# IMU_CAN_Speed_Converter_Board_rev2.net
KiCad netlist of a schematic drawn in EAGLE
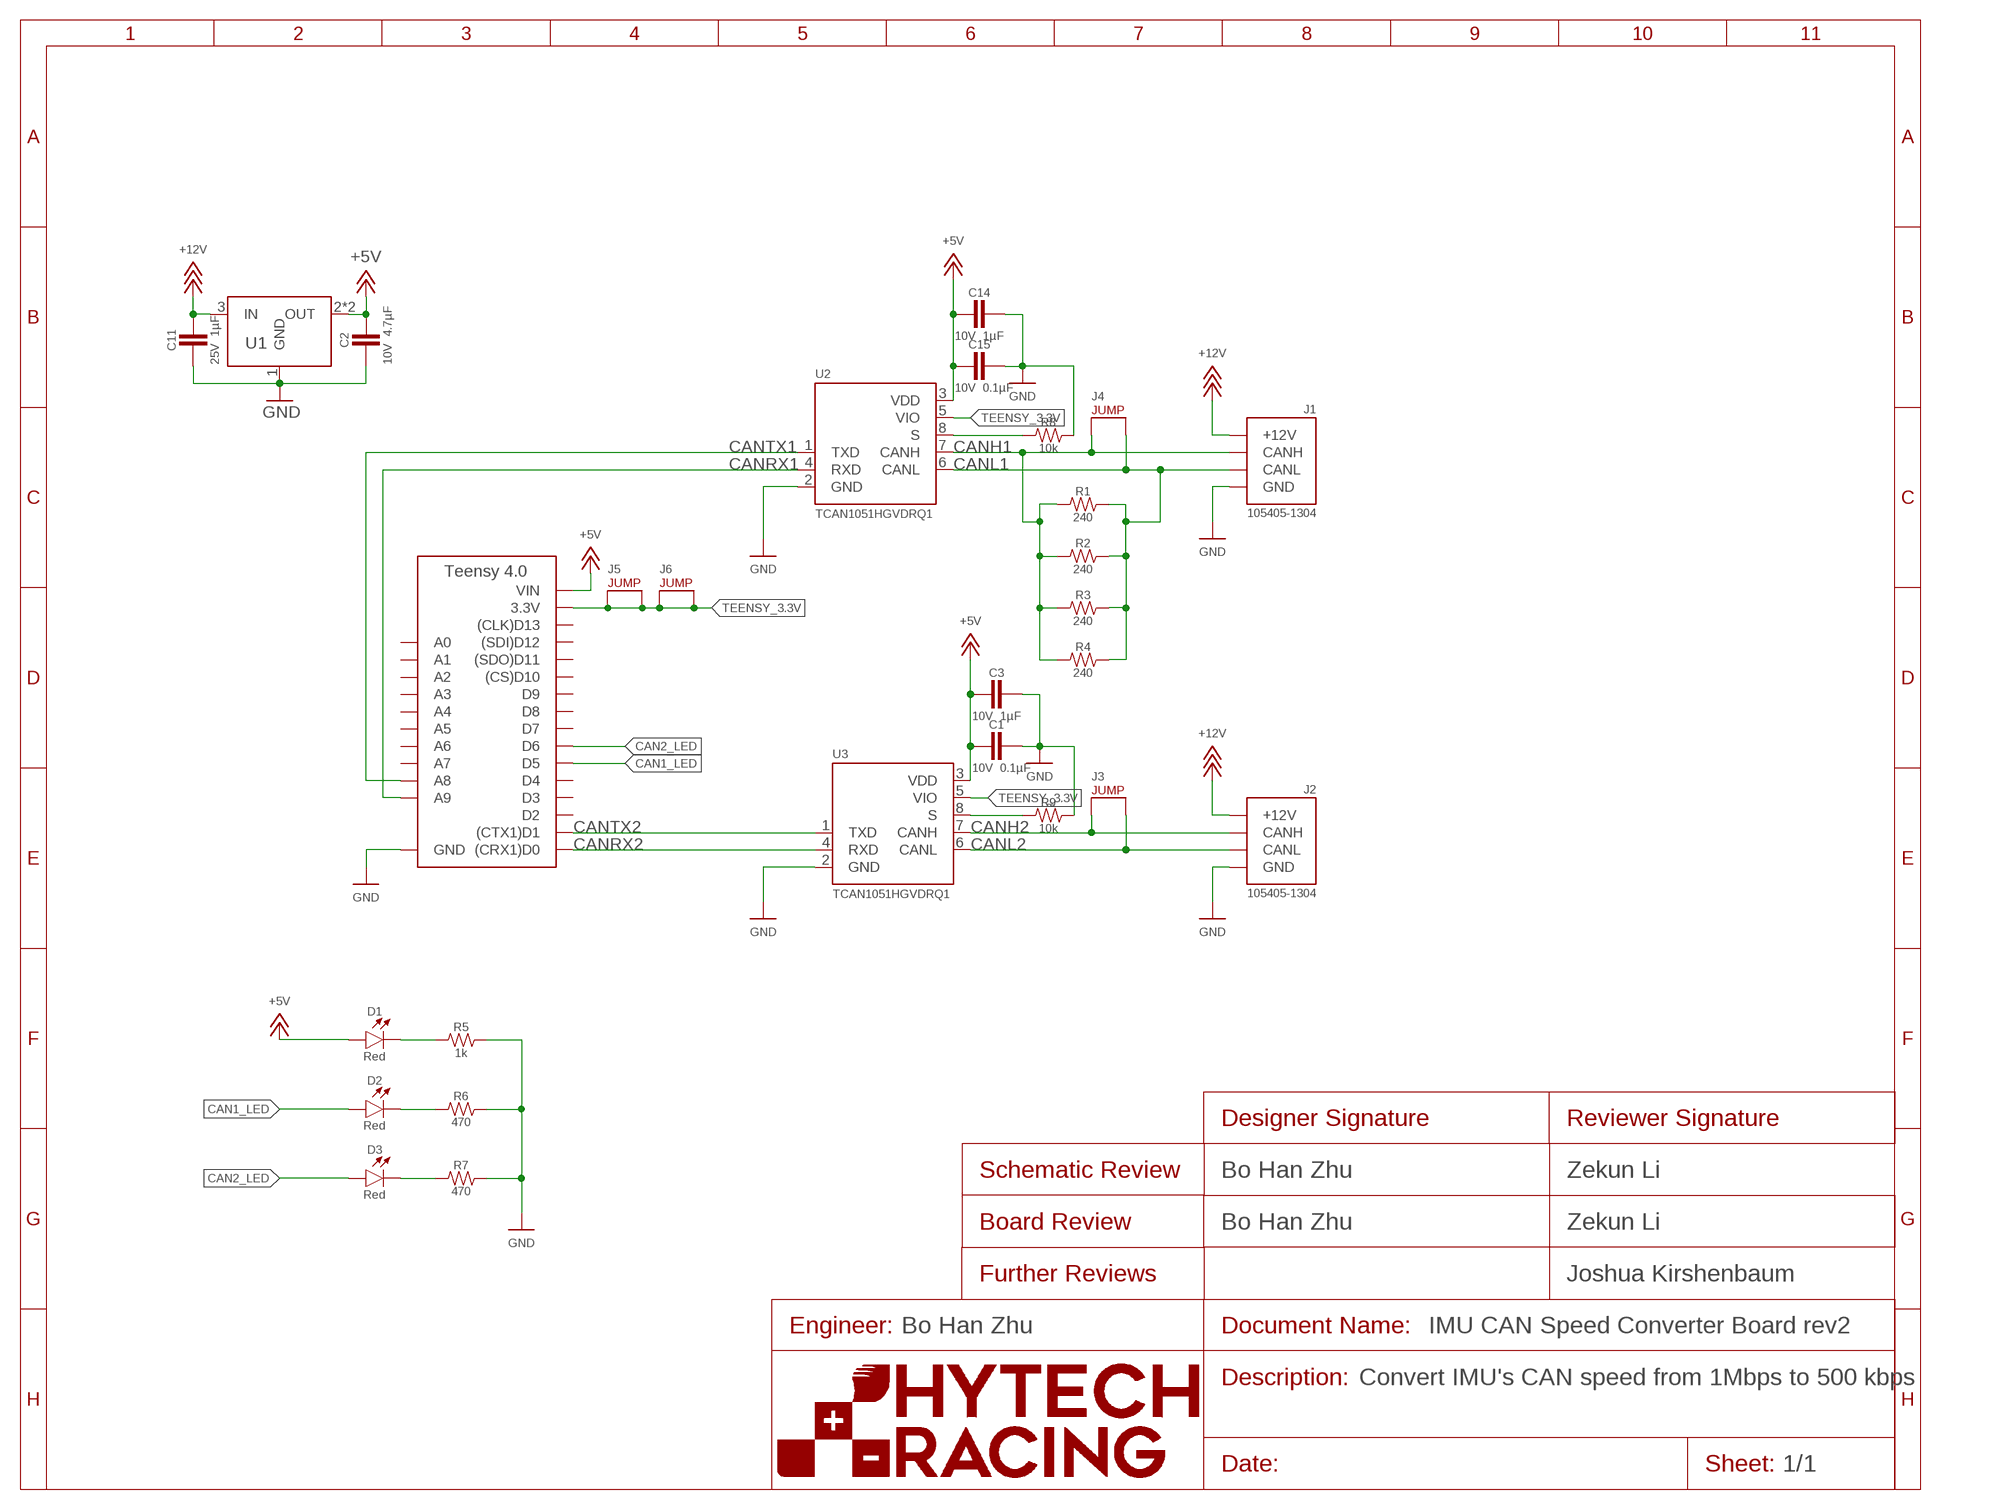
[diagram p0: schematic, sheet 1]

(export (version "E")
  (design (tool "Eeschema 10.0.6"))
  (components
    (comp (ref "A1")
      (value "TEENSY_4.0")
      (footprint "eagle-import:TEENSY_SHORT")
      (libsource (lib "eagle-import") (part "TEENSY_4.0"))
    )
    (comp (ref "C1")
      (value "CAPACITOR_0603_10V_0.1UF")
      (footprint "eagle-import:0603-CAP")
      (fields
        (field (name "CAPACITANCE") "0.1µF")
        (field (name "MANUFACTURER") "Vishay Vitramon")
        (field (name "MPN") "VJ0603Y104JXQPW1BC")
        (field (name "TOLERANCE") "5%")
        (field (name "VOLTAGE") "10V")
      )
      (libsource (lib "eagle-import") (part "CAPACITOR_?_060310V_0.1UF"))
    )
    (comp (ref "C2")
      (value "CAPACITOR_0603_10V_4.7UF")
      (footprint "eagle-import:0603-CAP")
      (fields
        (field (name "CAPACITANCE") "4.7µF")
        (field (name "MANUFACTURER") "Samsung Electro-Mechanics")
        (field (name "MPN") "CL10A475KP8NNNC")
        (field (name "TOLERANCE") "10%")
        (field (name "VOLTAGE") "10V")
      )
      (libsource (lib "eagle-import") (part "CAPACITOR_?_060310V_4.7UF"))
    )
    (comp (ref "C3")
      (value "CAPACITOR_0603_10V_1UF")
      (footprint "eagle-import:0603-CAP")
      (fields
        (field (name "CAPACITANCE") "1µF")
        (field (name "MANUFACTURER") "Yageo")
        (field (name "MPN") "CC0603KRX7R6BB105")
        (field (name "TOLERANCE") "10%")
        (field (name "VOLTAGE") "10V")
      )
      (libsource (lib "eagle-import") (part "CAPACITOR_?_060310V_1UF"))
    )
    (comp (ref "C11")
      (value "CAPACITOR_0603_25V_1UF")
      (footprint "eagle-import:0603-CAP")
      (fields
        (field (name "CAPACITANCE") "1µF")
        (field (name "MANUFACTURER") "Samsung Electro-Mechanics")
        (field (name "MPN") "CL10B105KA8NNNC")
        (field (name "TOLERANCE") "10%")
        (field (name "VOLTAGE") "25V")
      )
      (libsource (lib "eagle-import") (part "CAPACITOR_?_060325V_1UF"))
    )
    (comp (ref "C14")
      (value "CAPACITOR_0603_10V_1UF")
      (footprint "eagle-import:0603-CAP")
      (fields
        (field (name "CAPACITANCE") "1µF")
        (field (name "MANUFACTURER") "Yageo")
        (field (name "MPN") "CC0603KRX7R6BB105")
        (field (name "TOLERANCE") "10%")
        (field (name "VOLTAGE") "10V")
      )
      (libsource (lib "eagle-import") (part "CAPACITOR_?_060310V_1UF"))
    )
    (comp (ref "C15")
      (value "CAPACITOR_0603_10V_0.1UF")
      (footprint "eagle-import:0603-CAP")
      (fields
        (field (name "CAPACITANCE") "0.1µF")
        (field (name "MANUFACTURER") "Vishay Vitramon")
        (field (name "MPN") "VJ0603Y104JXQPW1BC")
        (field (name "TOLERANCE") "5%")
        (field (name "VOLTAGE") "10V")
      )
      (libsource (lib "eagle-import") (part "CAPACITOR_?_060310V_0.1UF"))
    )
    (comp (ref "D1")
      (value "LED_0603_RED")
      (footprint "eagle-import:0603-LED")
      (fields
        (field (name "COLOR") "Red")
        (field (name "MANUFACTURER") "Kingbright")
        (field (name "MPN") "APT1608SECK/J3-PRV")
      )
      (libsource (lib "eagle-import") (part "LED_?_0603RED"))
    )
    (comp (ref "D2")
      (value "LED_0603_RED")
      (footprint "eagle-import:0603-LED")
      (fields
        (field (name "COLOR") "Red")
        (field (name "MANUFACTURER") "Kingbright")
        (field (name "MPN") "APT1608SECK/J3-PRV")
      )
      (libsource (lib "eagle-import") (part "LED_?_0603RED"))
    )
    (comp (ref "D3")
      (value "LED_0603_RED")
      (footprint "eagle-import:0603-LED")
      (fields
        (field (name "COLOR") "Red")
        (field (name "MANUFACTURER") "Kingbright")
        (field (name "MPN") "APT1608SECK/J3-PRV")
      )
      (libsource (lib "eagle-import") (part "LED_?_0603RED"))
    )
    (comp (ref "J1")
      (value "CONNECTOR-CAN_NF_S_RA_BLACK")
      (footprint "eagle-import:MOLEX_NANOFIT_SMD_RIGHTANGLE_04")
      (fields (field (name "MANUFACTURER") "Molex") (field (name "MPN") "105405-1304"))
      (libsource (lib "eagle-import") (part "CONNECTOR-CAN_?_NF_S_RABLACK"))
    )
    (comp (ref "J2")
      (value "CONNECTOR-CAN_NF_S_RA_BLACK")
      (footprint "eagle-import:MOLEX_NANOFIT_SMD_RIGHTANGLE_04")
      (fields (field (name "MANUFACTURER") "Molex") (field (name "MPN") "105405-1304"))
      (libsource (lib "eagle-import") (part "CONNECTOR-CAN_?_NF_S_RABLACK"))
    )
    (comp (ref "J3")
      (value "JUMPER_1X02_")
      (footprint "eagle-import:1X02")
      (libsource (lib "eagle-import") (part "JUMPER_?_1X02"))
    )
    (comp (ref "J4")
      (value "JUMPER_1X02_")
      (footprint "eagle-import:1X02")
      (libsource (lib "eagle-import") (part "JUMPER_?_1X02"))
    )
    (comp (ref "J5")
      (value "JUMPER_1X02_")
      (footprint "eagle-import:1X02")
      (libsource (lib "eagle-import") (part "JUMPER_?_1X02"))
    )
    (comp (ref "J6")
      (value "JUMPER_1X02_")
      (footprint "eagle-import:1X02")
      (libsource (lib "eagle-import") (part "JUMPER_?_1X02"))
    )
    (comp (ref "R1")
      (value "RESISTOR_0603_240")
      (footprint "eagle-import:0603-RES")
      (fields
        (field (name "MANUFACTURER") "Yageo")
        (field (name "MPN") "RC0603FR-07240RL")
        (field (name "POWER") "0.1W")
        (field (name "RESISTANCE") "240")
      )
      (libsource (lib "eagle-import") (part "RESISTOR_?_0603240"))
    )
    (comp (ref "R2")
      (value "RESISTOR_0603_240")
      (footprint "eagle-import:0603-RES")
      (fields
        (field (name "MANUFACTURER") "Yageo")
        (field (name "MPN") "RC0603FR-07240RL")
        (field (name "POWER") "0.1W")
        (field (name "RESISTANCE") "240")
      )
      (libsource (lib "eagle-import") (part "RESISTOR_?_0603240"))
    )
    (comp (ref "R3")
      (value "RESISTOR_0603_240")
      (footprint "eagle-import:0603-RES")
      (fields
        (field (name "MANUFACTURER") "Yageo")
        (field (name "MPN") "RC0603FR-07240RL")
        (field (name "POWER") "0.1W")
        (field (name "RESISTANCE") "240")
      )
      (libsource (lib "eagle-import") (part "RESISTOR_?_0603240"))
    )
    (comp (ref "R4")
      (value "RESISTOR_0603_240")
      (footprint "eagle-import:0603-RES")
      (fields
        (field (name "MANUFACTURER") "Yageo")
        (field (name "MPN") "RC0603FR-07240RL")
        (field (name "POWER") "0.1W")
        (field (name "RESISTANCE") "240")
      )
      (libsource (lib "eagle-import") (part "RESISTOR_?_0603240"))
    )
    (comp (ref "R5")
      (value "RESISTOR_0603_1K")
      (footprint "eagle-import:0603-RES")
      (fields
        (field (name "MANUFACTURER") "Yageo")
        (field (name "MPN") "RC0603FR-071KL")
        (field (name "POWER") "0.1W")
        (field (name "RESISTANCE") "1k")
      )
      (libsource (lib "eagle-import") (part "RESISTOR_?_06031K"))
    )
    (comp (ref "R6")
      (value "RESISTOR_0603_470")
      (footprint "eagle-import:0603-RES")
      (fields
        (field (name "MANUFACTURER") "Panasonic Electronic Components")
        (field (name "MPN") "ERJ-PA3F4700V")
        (field (name "POWER") "0.25W")
        (field (name "RESISTANCE") "470")
      )
      (libsource (lib "eagle-import") (part "RESISTOR_?_0603470"))
    )
    (comp (ref "R7")
      (value "RESISTOR_0603_470")
      (footprint "eagle-import:0603-RES")
      (fields
        (field (name "MANUFACTURER") "Panasonic Electronic Components")
        (field (name "MPN") "ERJ-PA3F4700V")
        (field (name "POWER") "0.25W")
        (field (name "RESISTANCE") "470")
      )
      (libsource (lib "eagle-import") (part "RESISTOR_?_0603470"))
    )
    (comp (ref "R8")
      (value "RESISTOR_0603_10K")
      (footprint "eagle-import:0603-RES")
      (fields
        (field (name "MANUFACTURER") "Yageo")
        (field (name "MPN") "RC0603FR-0710KL")
        (field (name "POWER") "0.1W")
        (field (name "RESISTANCE") "10k")
      )
      (libsource (lib "eagle-import") (part "RESISTOR_?_060310K"))
    )
    (comp (ref "R9")
      (value "RESISTOR_0603_10K")
      (footprint "eagle-import:0603-RES")
      (fields
        (field (name "MANUFACTURER") "Yageo")
        (field (name "MPN") "RC0603FR-0710KL")
        (field (name "POWER") "0.1W")
        (field (name "RESISTANCE") "10k")
      )
      (libsource (lib "eagle-import") (part "RESISTOR_?_060310K"))
    )
    (comp (ref "U1")
      (value "VOLTAGE_REGULATOR_SOT223_5V")
      (footprint "eagle-import:SOT223")
      (fields (field (name "MANUFACTURER") "STMicroelectronics") (field (name "MPN") "LDL1117S50R"))
      (libsource (lib "eagle-import") (part "VOLTAGE_REGULATOR_?_SOT2235V"))
    )
    (comp (ref "U2")
      (value "TCAN1051HQV-Q1")
      (footprint "eagle-import:SOIC-08(NARROW,0.15_)")
      (fields (field (name "MANUFACTURER") "Texas Instruments") (field (name "MPN") "TCAN1051HGVDRQ1"))
      (libsource (lib "eagle-import") (part "TCAN1051V-Q1HQ"))
    )
    (comp (ref "U3")
      (value "TCAN1051HQV-Q1")
      (footprint "eagle-import:SOIC-08(NARROW,0.15_)")
      (fields (field (name "MANUFACTURER") "Texas Instruments") (field (name "MPN") "TCAN1051HGVDRQ1"))
      (libsource (lib "eagle-import") (part "TCAN1051V-Q1HQ"))
    )
  )
  (nets
    (net (code "1") (name "+5V") (class "Default")
      (node (ref "A1") (pin "VIN") (pinfunction "VIN_VIN") (pintype "power_in"))
      (node (ref "C1") (pin "2") (pinfunction "2_2") (pintype "passive"))
      (node (ref "C14") (pin "2") (pinfunction "2_2") (pintype "passive"))
      (node (ref "C15") (pin "2") (pinfunction "2_2") (pintype "passive"))
      (node (ref "C2") (pin "1") (pinfunction "1_1") (pintype "passive"))
      (node (ref "C3") (pin "2") (pinfunction "2_2") (pintype "passive"))
      (node (ref "D1") (pin "2") (pinfunction "A_2") (pintype "passive"))
      (node (ref "U1") (pin "2") (pinfunction "OUT_2") (pintype "power_in"))
      (node (ref "U1") (pin "4") (pinfunction "OUT_4") (pintype "power_in"))
      (node (ref "U2") (pin "3") (pinfunction "VDD_3") (pintype "power_in"))
      (node (ref "U3") (pin "3") (pinfunction "VDD_3") (pintype "power_in"))
    )
    (net (code "2") (name "+12V") (class "Default")
      (node (ref "C11") (pin "1") (pinfunction "1_1") (pintype "passive"))
      (node (ref "J1") (pin "1") (pinfunction "+12V_1") (pintype "power_in"))
      (node (ref "J2") (pin "1") (pinfunction "+12V_1") (pintype "power_in"))
      (node (ref "U1") (pin "3") (pinfunction "IN_3") (pintype "power_in"))
    )
    (net (code "3") (name "/CANH1") (class "Default")
      (node (ref "J1") (pin "4") (pinfunction "CANH_4") (pintype "bidirectional"))
      (node (ref "J4") (pin "1") (pinfunction "P$1_1") (pintype "passive"))
      (node (ref "R1") (pin "1") (pinfunction "1_1") (pintype "passive"))
      (node (ref "R2") (pin "1") (pinfunction "1_1") (pintype "passive"))
      (node (ref "R3") (pin "1") (pinfunction "1_1") (pintype "passive"))
      (node (ref "R4") (pin "1") (pinfunction "1_1") (pintype "passive"))
      (node (ref "U2") (pin "7") (pinfunction "CANH_7") (pintype "output"))
    )
    (net (code "4") (name "/CANH2") (class "Default")
      (node (ref "J2") (pin "4") (pinfunction "CANH_4") (pintype "bidirectional"))
      (node (ref "J3") (pin "1") (pinfunction "P$1_1") (pintype "passive"))
      (node (ref "U3") (pin "7") (pinfunction "CANH_7") (pintype "output"))
    )
    (net (code "5") (name "/CANL1") (class "Default")
      (node (ref "J1") (pin "3") (pinfunction "CANL_3") (pintype "bidirectional"))
      (node (ref "J4") (pin "2") (pinfunction "P$2_2") (pintype "passive"))
      (node (ref "R1") (pin "2") (pinfunction "2_2") (pintype "passive"))
      (node (ref "R2") (pin "2") (pinfunction "2_2") (pintype "passive"))
      (node (ref "R3") (pin "2") (pinfunction "2_2") (pintype "passive"))
      (node (ref "R4") (pin "2") (pinfunction "2_2") (pintype "passive"))
      (node (ref "U2") (pin "6") (pinfunction "CANL_6") (pintype "bidirectional"))
    )
    (net (code "6") (name "/CANL2") (class "Default")
      (node (ref "J2") (pin "3") (pinfunction "CANL_3") (pintype "bidirectional"))
      (node (ref "J3") (pin "2") (pinfunction "P$2_2") (pintype "passive"))
      (node (ref "U3") (pin "6") (pinfunction "CANL_6") (pintype "bidirectional"))
    )
    (net (code "7") (name "/CANRX1") (class "Default")
      (node (ref "A1") (pin "D23") (pinfunction "A9_D23") (pintype "bidirectional"))
      (node (ref "U2") (pin "4") (pinfunction "RXD_4") (pintype "output"))
    )
    (net (code "8") (name "/CANRX2") (class "Default")
      (node (ref "A1") (pin "D0") (pinfunction "(CRX1)D0_D0") (pintype "bidirectional"))
      (node (ref "U3") (pin "4") (pinfunction "RXD_4") (pintype "output"))
    )
    (net (code "9") (name "/CANTX1") (class "Default")
      (node (ref "A1") (pin "D22") (pinfunction "A8_D22") (pintype "bidirectional"))
      (node (ref "U2") (pin "1") (pinfunction "TXD_1") (pintype "input"))
    )
    (net (code "10") (name "/CANTX2") (class "Default")
      (node (ref "A1") (pin "D1") (pinfunction "(CTX1)D1_D1") (pintype "bidirectional"))
      (node (ref "U3") (pin "1") (pinfunction "TXD_1") (pintype "input"))
    )
    (net (code "11") (name "CAN1_LED") (class "Default")
      (node (ref "A1") (pin "D5") (pinfunction "D5_D5") (pintype "bidirectional"))
      (node (ref "D2") (pin "2") (pinfunction "A_2") (pintype "passive"))
    )
    (net (code "12") (name "CAN2_LED") (class "Default")
      (node (ref "A1") (pin "D6") (pinfunction "D6_D6") (pintype "bidirectional"))
      (node (ref "D3") (pin "2") (pinfunction "A_2") (pintype "passive"))
    )
    (net (code "13") (name "GND") (class "Default")
      (node (ref "A1") (pin "AGND/GND") (pinfunction "GND_AGND/GND") (pintype "power_in"))
      (node (ref "A1") (pin "GND") (pinfunction "GND_GND") (pintype "power_in"))
      (node (ref "C1") (pin "1") (pinfunction "1_1") (pintype "passive"))
      (node (ref "C11") (pin "2") (pinfunction "2_2") (pintype "passive"))
      (node (ref "C14") (pin "1") (pinfunction "1_1") (pintype "passive"))
      (node (ref "C15") (pin "1") (pinfunction "1_1") (pintype "passive"))
      (node (ref "C2") (pin "2") (pinfunction "2_2") (pintype "passive"))
      (node (ref "C3") (pin "1") (pinfunction "1_1") (pintype "passive"))
      (node (ref "J1") (pin "2") (pinfunction "GND_2") (pintype "power_in"))
      (node (ref "J2") (pin "2") (pinfunction "GND_2") (pintype "power_in"))
      (node (ref "R5") (pin "2") (pinfunction "2_2") (pintype "passive"))
      (node (ref "R6") (pin "2") (pinfunction "2_2") (pintype "passive"))
      (node (ref "R7") (pin "2") (pinfunction "2_2") (pintype "passive"))
      (node (ref "R8") (pin "2") (pinfunction "2_2") (pintype "passive"))
      (node (ref "R9") (pin "2") (pinfunction "2_2") (pintype "passive"))
      (node (ref "U1") (pin "1") (pinfunction "GND_1") (pintype "power_in"))
      (node (ref "U2") (pin "2") (pinfunction "GND_2") (pintype "power_in"))
      (node (ref "U3") (pin "2") (pinfunction "GND_2") (pintype "power_in"))
    )
    (net (code "14") (name "Net-(D1-C)") (class "Default")
      (node (ref "D1") (pin "1") (pinfunction "C_1") (pintype "passive"))
      (node (ref "R5") (pin "1") (pinfunction "1_1") (pintype "passive"))
    )
    (net (code "15") (name "Net-(D2-C)") (class "Default")
      (node (ref "D2") (pin "1") (pinfunction "C_1") (pintype "passive"))
      (node (ref "R6") (pin "1") (pinfunction "1_1") (pintype "passive"))
    )
    (net (code "16") (name "Net-(D3-C)") (class "Default")
      (node (ref "D3") (pin "1") (pinfunction "C_1") (pintype "passive"))
      (node (ref "R7") (pin "1") (pinfunction "1_1") (pintype "passive"))
    )
    (net (code "17") (name "Net-(U2-S)") (class "Default")
      (node (ref "R8") (pin "1") (pinfunction "1_1") (pintype "passive"))
      (node (ref "U2") (pin "8") (pinfunction "S_8") (pintype "input"))
    )
    (net (code "18") (name "Net-(U3-S)") (class "Default")
      (node (ref "R9") (pin "1") (pinfunction "1_1") (pintype "passive"))
      (node (ref "U3") (pin "8") (pinfunction "S_8") (pintype "input"))
    )
    (net (code "19") (name "TEENSY_3.3V") (class "Default")
      (node (ref "A1") (pin "3.3V") (pinfunction "3.3V_3.3V") (pintype "power_in"))
      (node (ref "J5") (pin "1") (pinfunction "P$1_1") (pintype "passive"))
      (node (ref "J5") (pin "2") (pinfunction "P$2_2") (pintype "passive"))
      (node (ref "J6") (pin "1") (pinfunction "P$1_1") (pintype "passive"))
      (node (ref "J6") (pin "2") (pinfunction "P$2_2") (pintype "passive"))
      (node (ref "U2") (pin "5") (pinfunction "VIO_5") (pintype "power_in"))
      (node (ref "U3") (pin "5") (pinfunction "VIO_5") (pintype "power_in"))
    )
    (net (code "20") (name "unconnected-(A1-(CLK)D13-PadD13)") (class "Default")
      (node (ref "A1") (pin "D13") (pinfunction "(CLK)D13_D13") (pintype "bidirectional"))
    )
    (net (code "21") (name "unconnected-(A1-(CS)D10-PadD10)") (class "Default")
      (node (ref "A1") (pin "D10") (pinfunction "(CS)D10_D10") (pintype "bidirectional"))
    )
    (net (code "22") (name "unconnected-(A1-(SDI)D12-PadD12)") (class "Default")
      (node (ref "A1") (pin "D12") (pinfunction "(SDI)D12_D12") (pintype "bidirectional"))
    )
    (net (code "23") (name "unconnected-(A1-(SDO)D11-PadD11)") (class "Default")
      (node (ref "A1") (pin "D11") (pinfunction "(SDO)D11_D11") (pintype "bidirectional"))
    )
    (net (code "24") (name "unconnected-(A1-A0-PadD14)") (class "Default")
      (node (ref "A1") (pin "D14") (pinfunction "A0_D14") (pintype "bidirectional"))
    )
    (net (code "25") (name "unconnected-(A1-A1-PadD15)") (class "Default")
      (node (ref "A1") (pin "D15") (pinfunction "A1_D15") (pintype "bidirectional"))
    )
    (net (code "26") (name "unconnected-(A1-A2-PadD16)") (class "Default")
      (node (ref "A1") (pin "D16") (pinfunction "A2_D16") (pintype "bidirectional"))
    )
    (net (code "27") (name "unconnected-(A1-A3-PadD17)") (class "Default")
      (node (ref "A1") (pin "D17") (pinfunction "A3_D17") (pintype "bidirectional"))
    )
    (net (code "28") (name "unconnected-(A1-A4-PadD18)") (class "Default")
      (node (ref "A1") (pin "D18") (pinfunction "A4_D18") (pintype "bidirectional"))
    )
    (net (code "29") (name "unconnected-(A1-A5-PadD19)") (class "Default")
      (node (ref "A1") (pin "D19") (pinfunction "A5_D19") (pintype "bidirectional"))
    )
    (net (code "30") (name "unconnected-(A1-A6-PadD20)") (class "Default")
      (node (ref "A1") (pin "D20") (pinfunction "A6_D20") (pintype "bidirectional"))
    )
    (net (code "31") (name "unconnected-(A1-A7-PadD21)") (class "Default")
      (node (ref "A1") (pin "D21") (pinfunction "A7_D21") (pintype "bidirectional"))
    )
    (net (code "32") (name "unconnected-(A1-PadD2)") (class "Default")
      (node (ref "A1") (pin "D2") (pinfunction "D2_D2") (pintype "bidirectional"))
    )
    (net (code "33") (name "unconnected-(A1-PadD3)") (class "Default")
      (node (ref "A1") (pin "D3") (pinfunction "D3_D3") (pintype "bidirectional"))
    )
    (net (code "34") (name "unconnected-(A1-PadD4)") (class "Default")
      (node (ref "A1") (pin "D4") (pinfunction "D4_D4") (pintype "bidirectional"))
    )
    (net (code "35") (name "unconnected-(A1-PadD7)") (class "Default")
      (node (ref "A1") (pin "D7") (pinfunction "D7_D7") (pintype "bidirectional"))
    )
    (net (code "36") (name "unconnected-(A1-PadD8)") (class "Default")
      (node (ref "A1") (pin "D8") (pinfunction "D8_D8") (pintype "bidirectional"))
    )
    (net (code "37") (name "unconnected-(A1-PadD9)") (class "Default")
      (node (ref "A1") (pin "D9") (pinfunction "D9_D9") (pintype "bidirectional"))
    )
  )
)
